# spinsmoothly.net
KiCad netlist of a schematic drawn in EAGLE
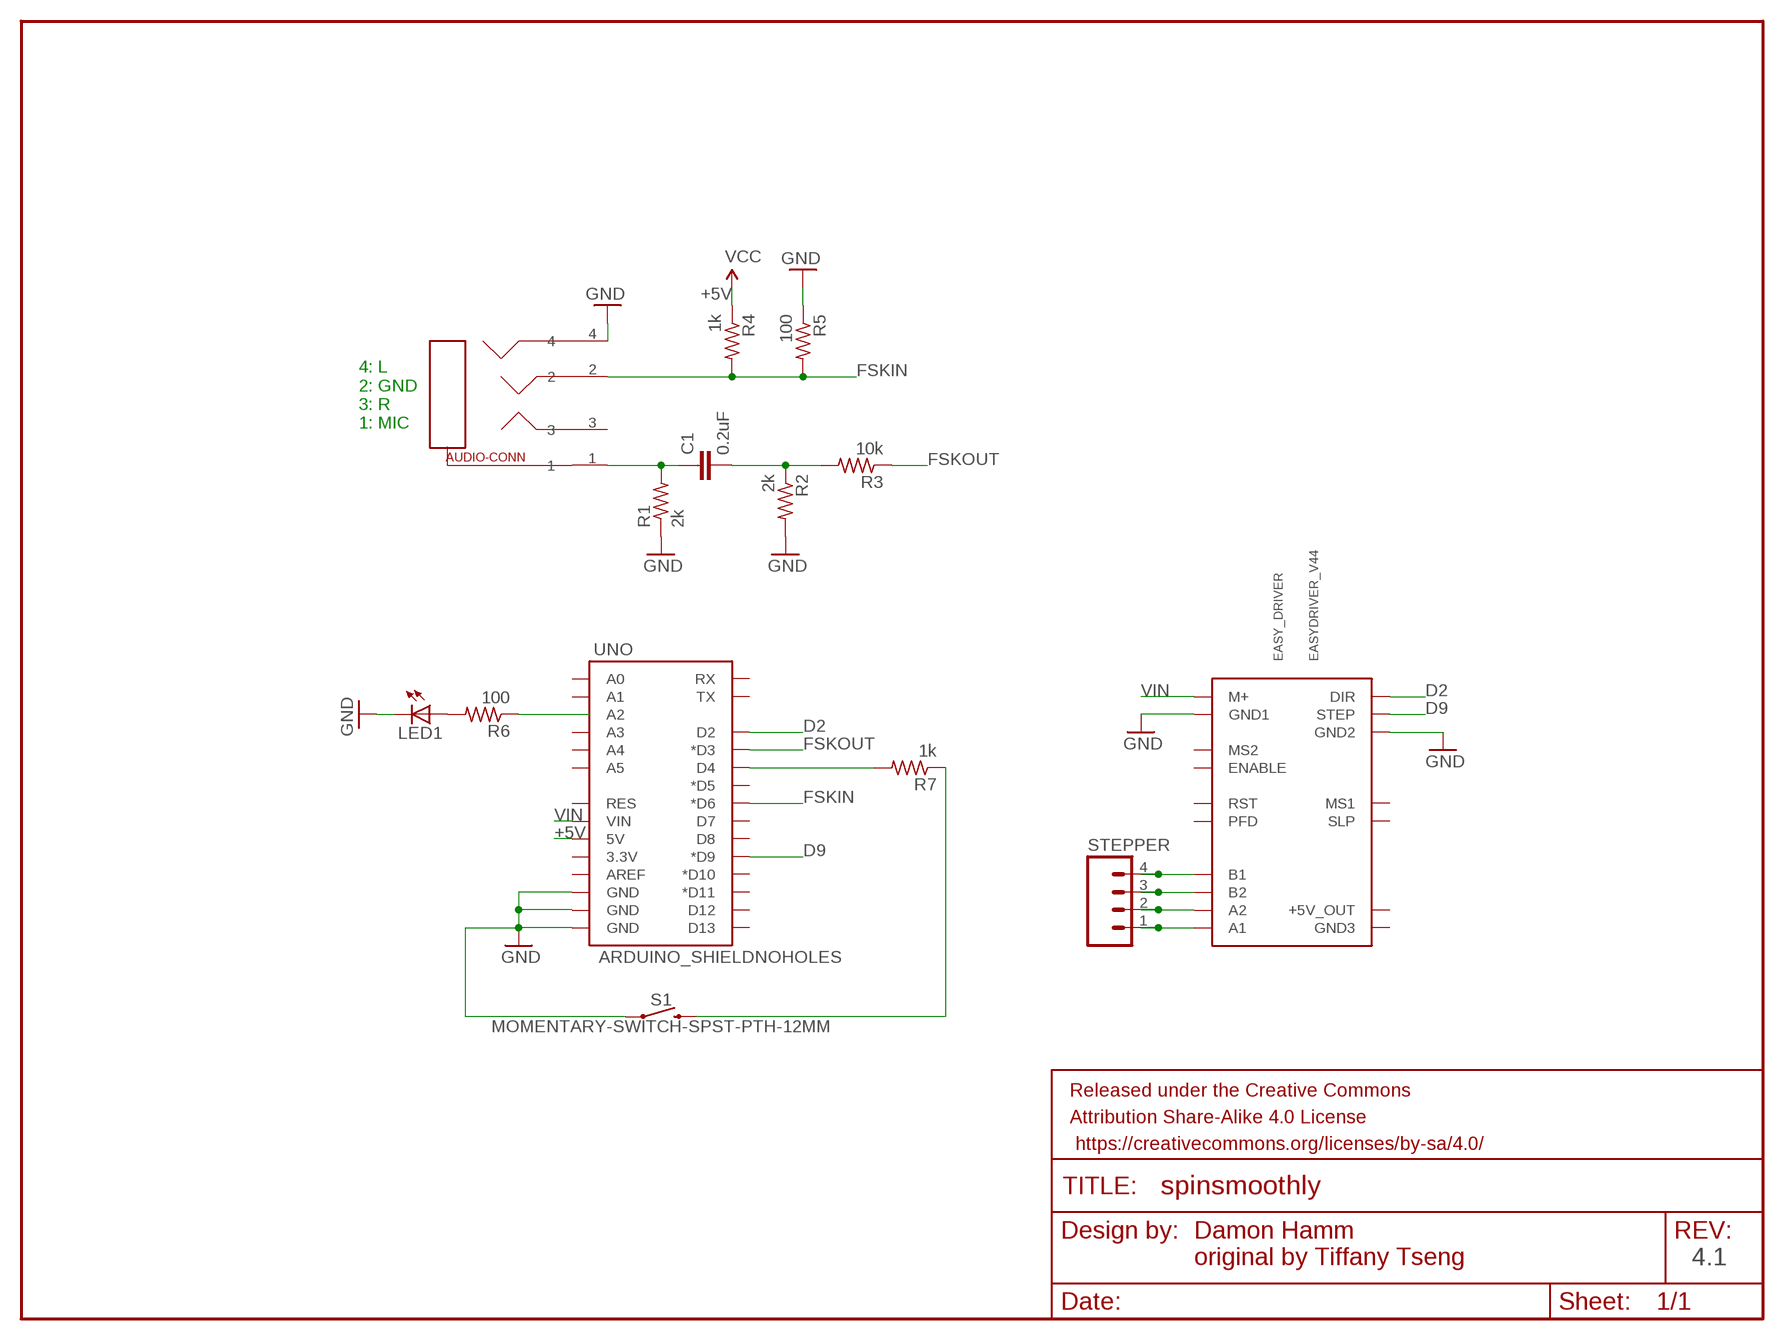
[diagram p0: schematic, sheet 1]

(export (version "E")
  (design (tool "Eeschema 10.0.6"))
  (components
    (comp (ref "C1")
      (value "0.2uF")
      (footprint "eagle-import:1206")
      (libsource (lib "eagle-import") (part "CAP1206"))
    )
    (comp (ref "EASY_DRIVER")
      (value "EASYDRIVER_V44")
      (footprint "eagle-import:EASYDRIVER_V44")
      (libsource (lib "eagle-import") (part "EASYDRIVER_V44"))
    )
    (comp (ref "FRAME1")
      (value "FRAME-LETTER")
      (footprint "eagle-import:CREATIVE_COMMONS")
      (libsource (lib "eagle-import") (part "FRAME-LETTER"))
    )
    (comp (ref "LED1")
      (value "LED1206")
      (footprint "eagle-import:1206")
      (libsource (lib "eagle-import") (part "LED1206"))
    )
    (comp (ref "R1")
      (value "2k")
      (footprint "eagle-import:R1206")
      (libsource (lib "eagle-import") (part "R-US_R1206"))
    )
    (comp (ref "R2")
      (value "2k")
      (footprint "eagle-import:R1206")
      (libsource (lib "eagle-import") (part "R-US_R1206"))
    )
    (comp (ref "R3")
      (value "10k")
      (footprint "eagle-import:R1206")
      (libsource (lib "eagle-import") (part "R-US_R1206"))
    )
    (comp (ref "R4")
      (value "1k")
      (footprint "eagle-import:R1206")
      (libsource (lib "eagle-import") (part "R-US_R1206"))
    )
    (comp (ref "R5")
      (value "100")
      (footprint "eagle-import:R1206")
      (libsource (lib "eagle-import") (part "R-US_R1206"))
    )
    (comp (ref "R6")
      (value "100")
      (footprint "eagle-import:R1206")
      (libsource (lib "eagle-import") (part "R-US_R1206"))
    )
    (comp (ref "R7")
      (value "1k")
      (footprint "eagle-import:R1206")
      (libsource (lib "eagle-import") (part "R-US_R1206"))
    )
    (comp (ref "S1")
      (value "MOMENTARY-SWITCH-SPST-PTH-12MM")
      (footprint "eagle-import:TACTILE_SWITCH_PTH_12MM")
      (libsource (lib "eagle-import") (part "MOMENTARY-SWITCH-SPST-PTH-12MM"))
    )
    (comp (ref "STEPPER")
      (value "M04PTH")
      (footprint "eagle-import:1X04")
      (libsource (lib "eagle-import") (part "M04PTH"))
    )
    (comp (ref "U$1")
      (value "SJ-43514")
      (footprint "eagle-import:SJ-43514")
      (libsource (lib "eagle-import") (part "SJ-43514"))
    )
    (comp (ref "UNO")
      (value "ARDUINO_SHIELDNOHOLES")
      (footprint "eagle-import:DUEMILANOVE_SHIELD_NOHOLES")
      (libsource (lib "eagle-import") (part "ARDUINO_SHIELDNOHOLES"))
    )
  )
  (nets
    (net (code "1") (name "/1") (class "Default")
      (node (ref "C1") (pin "1") (pinfunction "1_1") (pintype "passive"))
      (node (ref "R1") (pin "2") (pinfunction "2_2") (pintype "passive"))
      (node (ref "U$1") (pin "1") (pinfunction "1_1") (pintype "bidirectional"))
    )
    (net (code "2") (name "/D2") (class "Default")
      (node (ref "EASY_DRIVER") (pin "DIR") (pinfunction "DIR_DIR") (pintype "bidirectional"))
      (node (ref "UNO") (pin "D2") (pinfunction "D2_D2") (pintype "bidirectional"))
    )
    (net (code "3") (name "/D9") (class "Default")
      (node (ref "EASY_DRIVER") (pin "STEP") (pinfunction "STEP_STEP") (pintype "bidirectional"))
      (node (ref "UNO") (pin "D9") (pinfunction "*D9_D9") (pintype "bidirectional"))
    )
    (net (code "4") (name "/FSKIN") (class "Default")
      (node (ref "R4") (pin "2") (pinfunction "2_2") (pintype "passive"))
      (node (ref "R5") (pin "2") (pinfunction "2_2") (pintype "passive"))
      (node (ref "U$1") (pin "2") (pinfunction "2_2") (pintype "bidirectional"))
      (node (ref "UNO") (pin "D6") (pinfunction "*D6_D6") (pintype "bidirectional"))
    )
    (net (code "5") (name "/FSKOUT") (class "Default")
      (node (ref "R3") (pin "1") (pinfunction "1_1") (pintype "passive"))
      (node (ref "UNO") (pin "D3") (pinfunction "*D3_D3") (pintype "bidirectional"))
    )
    (net (code "6") (name "/VIN") (class "Default")
      (node (ref "EASY_DRIVER") (pin "M+") (pinfunction "M+_M+") (pintype "bidirectional"))
      (node (ref "UNO") (pin "VIN") (pinfunction "VIN_VIN") (pintype "bidirectional"))
    )
    (net (code "7") (name "GND") (class "Default")
      (node (ref "EASY_DRIVER") (pin "GND1") (pinfunction "GND1_GND1") (pintype "bidirectional"))
      (node (ref "EASY_DRIVER") (pin "GND2") (pinfunction "GND2_GND2") (pintype "bidirectional"))
      (node (ref "LED1") (pin "2") (pinfunction "C_2") (pintype "passive"))
      (node (ref "R1") (pin "1") (pinfunction "1_1") (pintype "passive"))
      (node (ref "R2") (pin "2") (pinfunction "2_2") (pintype "passive"))
      (node (ref "R5") (pin "1") (pinfunction "1_1") (pintype "passive"))
      (node (ref "S1") (pin "1") (pinfunction "1_1") (pintype "passive"))
      (node (ref "U$1") (pin "4") (pinfunction "4_4") (pintype "bidirectional"))
      (node (ref "UNO") (pin "GND@0") (pinfunction "GND_GND@0") (pintype "bidirectional"))
      (node (ref "UNO") (pin "GND@1") (pinfunction "GND_GND@1") (pintype "bidirectional"))
      (node (ref "UNO") (pin "GND@2") (pinfunction "GND_GND@2") (pintype "bidirectional"))
    )
    (net (code "8") (name "Net-(C1-Pad2)") (class "Default")
      (node (ref "C1") (pin "2") (pinfunction "2_2") (pintype "passive"))
      (node (ref "R2") (pin "1") (pinfunction "1_1") (pintype "passive"))
      (node (ref "R3") (pin "2") (pinfunction "2_2") (pintype "passive"))
    )
    (net (code "9") (name "Net-(EASY_DRIVER-PadA1)") (class "Default")
      (node (ref "EASY_DRIVER") (pin "A1") (pinfunction "A1_A1") (pintype "bidirectional"))
      (node (ref "STEPPER") (pin "1") (pinfunction "1_1") (pintype "passive"))
    )
    (net (code "10") (name "Net-(EASY_DRIVER-PadA2)") (class "Default")
      (node (ref "EASY_DRIVER") (pin "A2") (pinfunction "A2_A2") (pintype "bidirectional"))
      (node (ref "STEPPER") (pin "2") (pinfunction "2_2") (pintype "passive"))
    )
    (net (code "11") (name "Net-(EASY_DRIVER-PadB1)") (class "Default")
      (node (ref "EASY_DRIVER") (pin "B1") (pinfunction "B1_B1") (pintype "bidirectional"))
      (node (ref "STEPPER") (pin "4") (pinfunction "4_4") (pintype "passive"))
    )
    (net (code "12") (name "Net-(EASY_DRIVER-PadB2)") (class "Default")
      (node (ref "EASY_DRIVER") (pin "B2") (pinfunction "B2_B2") (pintype "bidirectional"))
      (node (ref "STEPPER") (pin "3") (pinfunction "3_3") (pintype "passive"))
    )
    (net (code "13") (name "Net-(LED1-A)") (class "Default")
      (node (ref "LED1") (pin "1") (pinfunction "A_1") (pintype "passive"))
      (node (ref "R6") (pin "2") (pinfunction "2_2") (pintype "passive"))
    )
    (net (code "14") (name "Net-(R7-Pad2)") (class "Default")
      (node (ref "R7") (pin "2") (pinfunction "2_2") (pintype "passive"))
      (node (ref "UNO") (pin "D4") (pinfunction "D4_D4") (pintype "bidirectional"))
    )
    (net (code "15") (name "Net-(S1-2)") (class "Default")
      (node (ref "R7") (pin "1") (pinfunction "1_1") (pintype "passive"))
      (node (ref "S1") (pin "3") (pinfunction "2_3") (pintype "passive"))
    )
    (net (code "16") (name "VCC") (class "Default")
      (node (ref "R4") (pin "1") (pinfunction "1_1") (pintype "passive"))
      (node (ref "UNO") (pin "5V") (pinfunction "5V_5V") (pintype "bidirectional"))
    )
    (net (code "17") (name "unconnected-(EASY_DRIVER-+5V_OUT-PadP$11)") (class "Default")
      (node (ref "EASY_DRIVER") (pin "P$11") (pinfunction "+5V_OUT_P$11") (pintype "bidirectional"))
    )
    (net (code "18") (name "unconnected-(EASY_DRIVER-PadENABLE)") (class "Default")
      (node (ref "EASY_DRIVER") (pin "ENABLE") (pinfunction "ENABLE_ENABLE") (pintype "bidirectional"))
    )
    (net (code "19") (name "unconnected-(EASY_DRIVER-PadGND3)") (class "Default")
      (node (ref "EASY_DRIVER") (pin "GND3") (pinfunction "GND3_GND3") (pintype "bidirectional"))
    )
    (net (code "20") (name "unconnected-(EASY_DRIVER-PadMS1)") (class "Default")
      (node (ref "EASY_DRIVER") (pin "MS1") (pinfunction "MS1_MS1") (pintype "bidirectional"))
    )
    (net (code "21") (name "unconnected-(EASY_DRIVER-PadMS2)") (class "Default")
      (node (ref "EASY_DRIVER") (pin "MS2") (pinfunction "MS2_MS2") (pintype "bidirectional"))
    )
    (net (code "22") (name "unconnected-(EASY_DRIVER-PadPFD)") (class "Default")
      (node (ref "EASY_DRIVER") (pin "PFD") (pinfunction "PFD_PFD") (pintype "bidirectional"))
    )
    (net (code "23") (name "unconnected-(EASY_DRIVER-PadRST)") (class "Default")
      (node (ref "EASY_DRIVER") (pin "RST") (pinfunction "RST_RST") (pintype "bidirectional"))
    )
    (net (code "24") (name "unconnected-(EASY_DRIVER-SLP-PadSLEEP)") (class "Default")
      (node (ref "EASY_DRIVER") (pin "SLEEP") (pinfunction "SLP_SLEEP") (pintype "bidirectional"))
    )
    (net (code "25") (name "unconnected-(R6-Pad1)") (class "Default")
      (node (ref "R6") (pin "1") (pinfunction "1_1") (pintype "passive"))
    )
    (net (code "26") (name "unconnected-(U$1-Pad3)") (class "Default")
      (node (ref "U$1") (pin "3") (pinfunction "3_3") (pintype "bidirectional"))
    )
    (net (code "27") (name "unconnected-(UNO-*D5-PadD5)") (class "Default")
      (node (ref "UNO") (pin "D5") (pinfunction "*D5_D5") (pintype "bidirectional"))
    )
    (net (code "28") (name "unconnected-(UNO-*D10-PadD10)") (class "Default")
      (node (ref "UNO") (pin "D10") (pinfunction "*D10_D10") (pintype "bidirectional"))
    )
    (net (code "29") (name "unconnected-(UNO-*D11-PadD11)") (class "Default")
      (node (ref "UNO") (pin "D11") (pinfunction "*D11_D11") (pintype "bidirectional"))
    )
    (net (code "30") (name "unconnected-(UNO-Pad3.3V)") (class "Default")
      (node (ref "UNO") (pin "3.3V") (pinfunction "3.3V_3.3V") (pintype "bidirectional"))
    )
    (net (code "31") (name "unconnected-(UNO-PadA0)") (class "Default")
      (node (ref "UNO") (pin "A0") (pinfunction "A0_A0") (pintype "bidirectional"))
    )
    (net (code "32") (name "unconnected-(UNO-PadA1)") (class "Default")
      (node (ref "UNO") (pin "A1") (pinfunction "A1_A1") (pintype "bidirectional"))
    )
    (net (code "33") (name "unconnected-(UNO-PadA2)") (class "Default")
      (node (ref "UNO") (pin "A2") (pinfunction "A2_A2") (pintype "bidirectional"))
    )
    (net (code "34") (name "unconnected-(UNO-PadA3)") (class "Default")
      (node (ref "UNO") (pin "A3") (pinfunction "A3_A3") (pintype "bidirectional"))
    )
    (net (code "35") (name "unconnected-(UNO-PadA4)") (class "Default")
      (node (ref "UNO") (pin "A4") (pinfunction "A4_A4") (pintype "bidirectional"))
    )
    (net (code "36") (name "unconnected-(UNO-PadA5)") (class "Default")
      (node (ref "UNO") (pin "A5") (pinfunction "A5_A5") (pintype "bidirectional"))
    )
    (net (code "37") (name "unconnected-(UNO-PadAREF)") (class "Default")
      (node (ref "UNO") (pin "AREF") (pinfunction "AREF_AREF") (pintype "bidirectional"))
    )
    (net (code "38") (name "unconnected-(UNO-PadD7)") (class "Default")
      (node (ref "UNO") (pin "D7") (pinfunction "D7_D7") (pintype "bidirectional"))
    )
    (net (code "39") (name "unconnected-(UNO-PadD8)") (class "Default")
      (node (ref "UNO") (pin "D8") (pinfunction "D8_D8") (pintype "bidirectional"))
    )
    (net (code "40") (name "unconnected-(UNO-PadD12)") (class "Default")
      (node (ref "UNO") (pin "D12") (pinfunction "D12_D12") (pintype "bidirectional"))
    )
    (net (code "41") (name "unconnected-(UNO-PadD13)") (class "Default")
      (node (ref "UNO") (pin "D13") (pinfunction "D13_D13") (pintype "bidirectional"))
    )
    (net (code "42") (name "unconnected-(UNO-PadRES)") (class "Default")
      (node (ref "UNO") (pin "RES") (pinfunction "RES_RES") (pintype "bidirectional"))
    )
    (net (code "43") (name "unconnected-(UNO-PadRX)") (class "Default")
      (node (ref "UNO") (pin "RX") (pinfunction "RX_RX") (pintype "bidirectional"))
    )
    (net (code "44") (name "unconnected-(UNO-PadTX)") (class "Default")
      (node (ref "UNO") (pin "TX") (pinfunction "TX_TX") (pintype "bidirectional"))
    )
  )
)
